# dengenver2_0.net
KiCad netlist of a schematic drawn in EAGLE
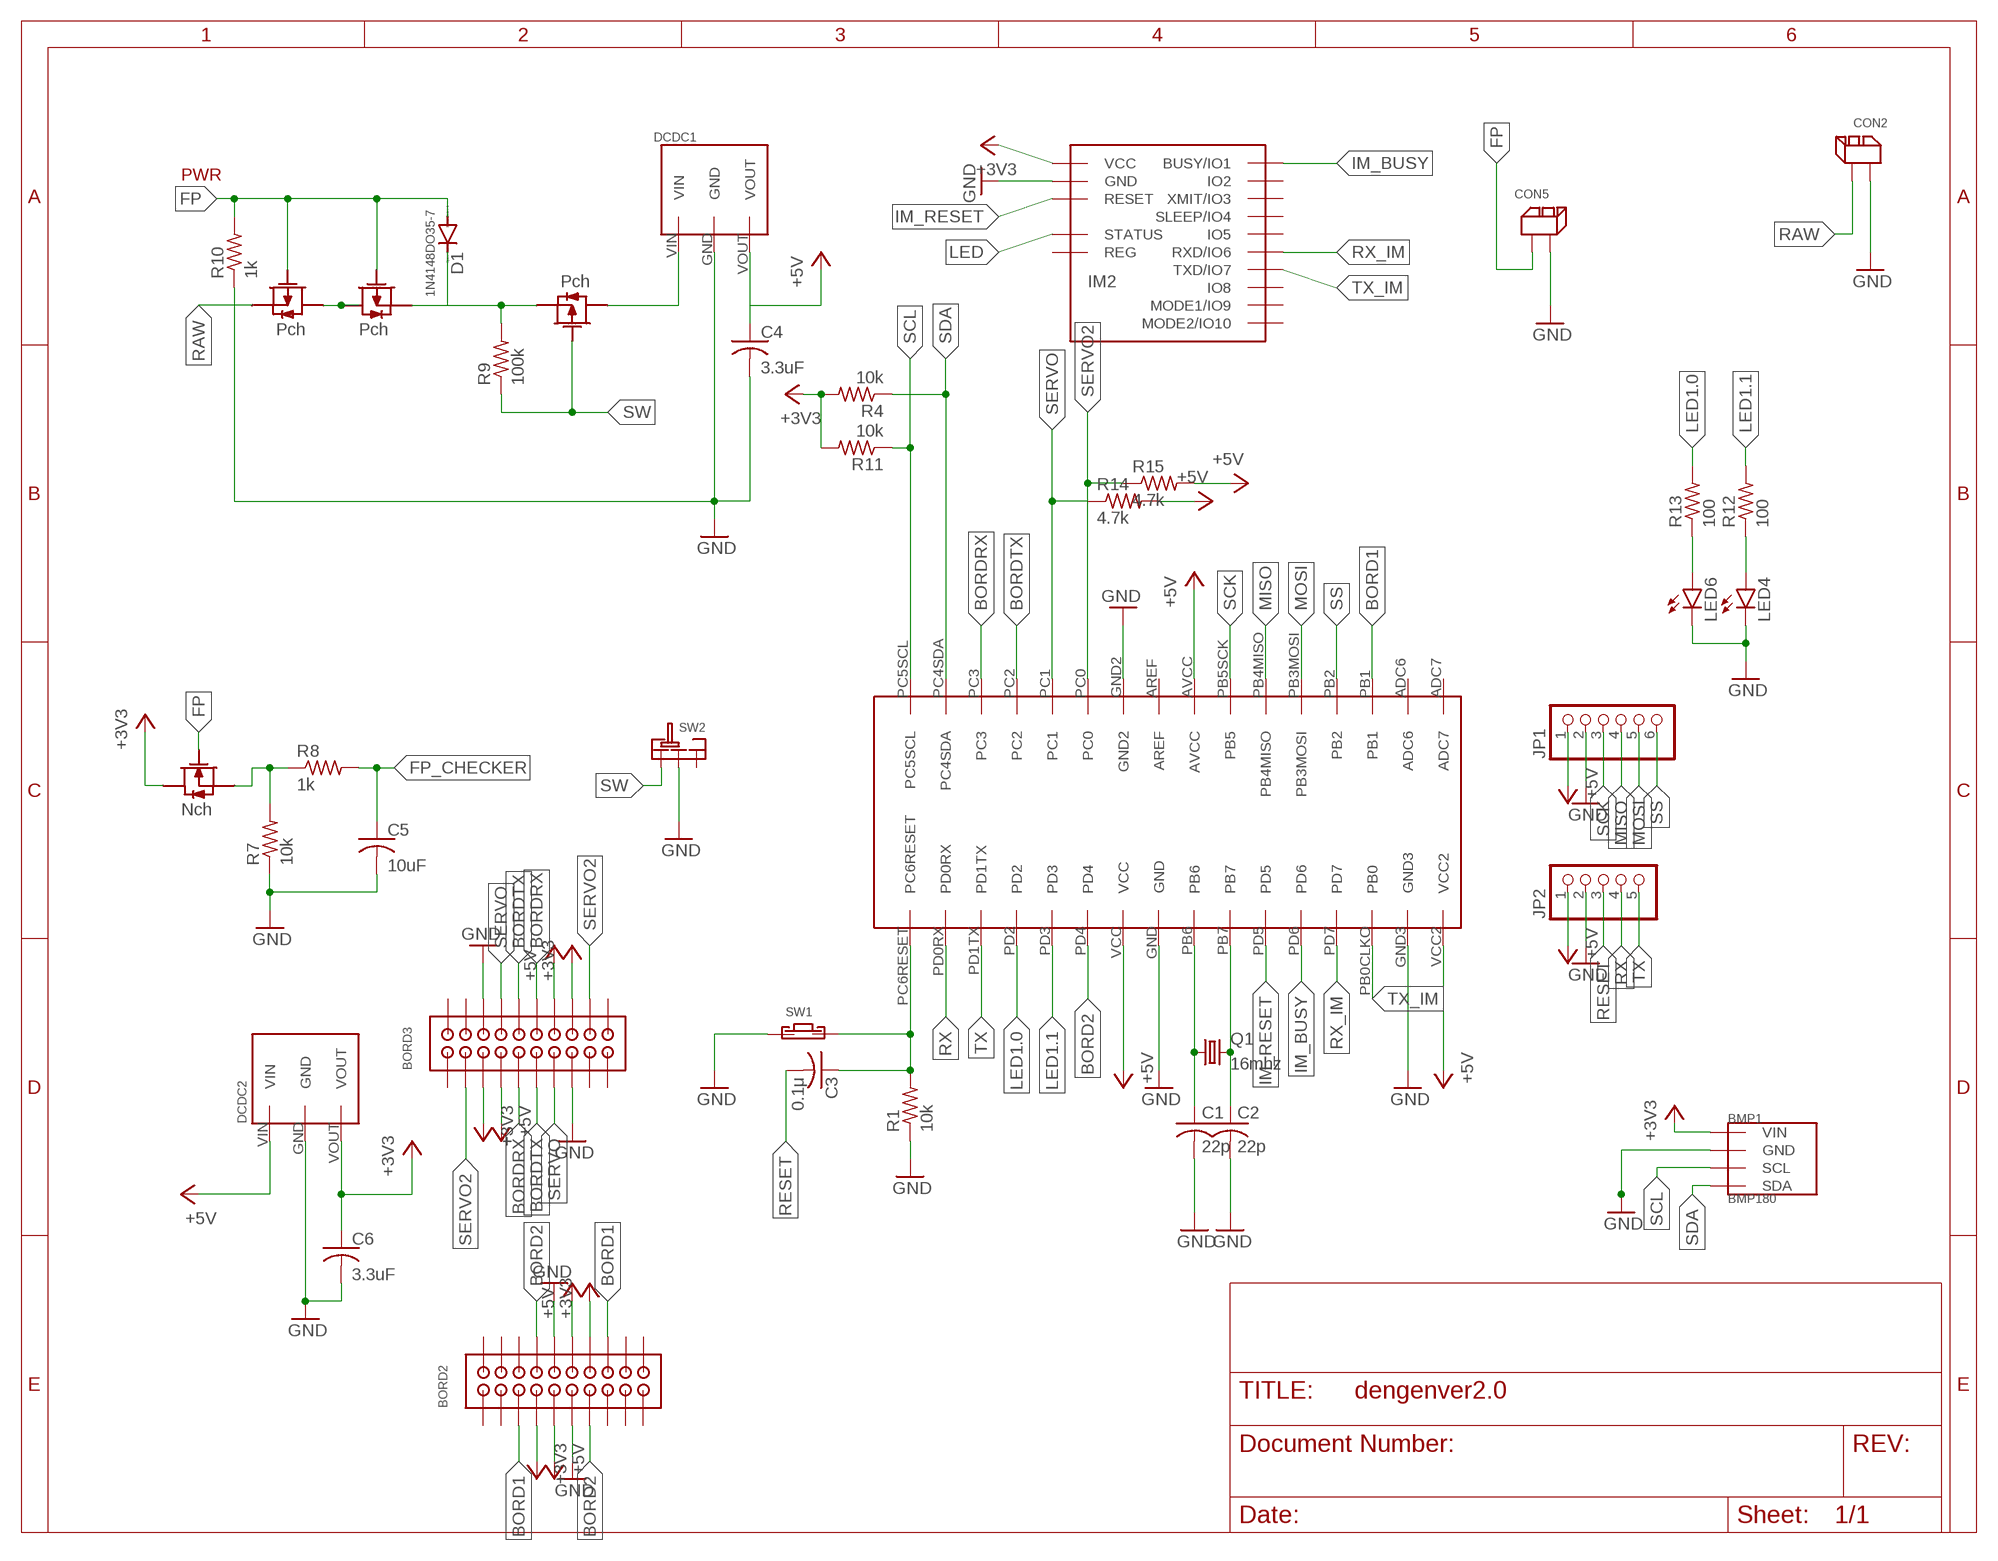
[diagram p0: schematic, sheet 1]

(export (version "E")
  (design (tool "Eeschema 10.0.6"))
  (components
    (comp (ref "BMP1")
      (value "BMP180")
      (footprint "eagle-import:GY-68")
      (libsource (lib "eagle-import") (part "BMP180"))
    )
    (comp (ref "BORD2")
      (value "2X10")
      (footprint "eagle-import:2X10")
      (libsource (lib "eagle-import") (part "2X10"))
    )
    (comp (ref "BORD3")
      (value "2X10")
      (footprint "eagle-import:2X10")
      (libsource (lib "eagle-import") (part "2X10"))
    )
    (comp (ref "C1")
      (value "22p")
      (footprint "eagle-import:C1608")
      (libsource (lib "eagle-import") (part "C-USC1608"))
    )
    (comp (ref "C2")
      (value "22p")
      (footprint "eagle-import:C1608")
      (libsource (lib "eagle-import") (part "C-USC1608"))
    )
    (comp (ref "C3")
      (value "0.1μ")
      (footprint "eagle-import:C1608")
      (libsource (lib "eagle-import") (part "C-USC1608"))
    )
    (comp (ref "C4")
      (value "3.3uF")
      (footprint "eagle-import:C1608")
      (libsource (lib "eagle-import") (part "C-USC1608"))
    )
    (comp (ref "C5")
      (value "10uF")
      (footprint "eagle-import:C1608")
      (libsource (lib "eagle-import") (part "C-USC1608"))
    )
    (comp (ref "C6")
      (value "3.3uF")
      (footprint "eagle-import:C1608")
      (libsource (lib "eagle-import") (part "C-USC1608"))
    )
    (comp (ref "CON2")
      (value "2PIN")
      (footprint "eagle-import:2PIN")
      (libsource (lib "eagle-import") (part "2PIN"))
    )
    (comp (ref "CON5")
      (value "2PIN")
      (footprint "eagle-import:2PIN")
      (libsource (lib "eagle-import") (part "2PIN"))
    )
    (comp (ref "D1")
      (value "1N4148DO35-7")
      (footprint "eagle-import:DO35-7")
      (libsource (lib "eagle-import") (part "1N4148DO35-7"))
    )
    (comp (ref "DCDC1")
      (value "5V1A_M78AR05-1")
      (footprint "eagle-import:5V1A_M78AR05-1")
      (libsource (lib "eagle-import") (part "5V1A_M78AR05-1"))
    )
    (comp (ref "DCDC2")
      (value "3.3V1A_M78AR033-1")
      (footprint "eagle-import:3.3V1A_M78AR033-1")
      (libsource (lib "eagle-import") (part "3.3V1A_M78AR033-1"))
    )
    (comp (ref "IM2")
      (value "IM920_IM920C")
      (footprint "eagle-import:IM920_IM920C")
      (libsource (lib "eagle-import") (part "IM920_IM920C"))
    )
    (comp (ref "JP1")
      (value "PINHD-1X6")
      (footprint "eagle-import:1X06")
      (libsource (lib "eagle-import") (part "PINHD-1X6"))
    )
    (comp (ref "JP2")
      (value "PINHD-1X5")
      (footprint "eagle-import:1X05")
      (libsource (lib "eagle-import") (part "PINHD-1X5"))
    )
    (comp (ref "LED4")
      (value "LED5MM")
      (footprint "eagle-import:LED5MM")
      (libsource (lib "eagle-import") (part "LED5MM"))
    )
    (comp (ref "LED6")
      (value "LED5MM")
      (footprint "eagle-import:LED5MM")
      (libsource (lib "eagle-import") (part "LED5MM"))
    )
    (comp (ref "Q1")
      (value "16mhz")
      (footprint "eagle-import:HC49UP")
      (libsource (lib "eagle-import") (part "CRYSTALHC49UP"))
    )
    (comp (ref "R1")
      (value "10k")
      (footprint "eagle-import:R0603")
      (libsource (lib "eagle-import") (part "R-US_R0603"))
    )
    (comp (ref "R4")
      (value "10k")
      (footprint "eagle-import:R0603")
      (libsource (lib "eagle-import") (part "R-US_R0603"))
    )
    (comp (ref "R7")
      (value "10k")
      (footprint "eagle-import:R0603")
      (libsource (lib "eagle-import") (part "R-US_R0603"))
    )
    (comp (ref "R8")
      (value "1k")
      (footprint "eagle-import:R0603")
      (libsource (lib "eagle-import") (part "R-US_R0603"))
    )
    (comp (ref "R9")
      (value "100k")
      (footprint "eagle-import:R0603")
      (libsource (lib "eagle-import") (part "R-US_R0603"))
    )
    (comp (ref "R10")
      (value "1k")
      (footprint "eagle-import:R0603")
      (libsource (lib "eagle-import") (part "R-US_R0603"))
    )
    (comp (ref "R11")
      (value "10k")
      (footprint "eagle-import:R0603")
      (libsource (lib "eagle-import") (part "R-US_R0603"))
    )
    (comp (ref "R12")
      (value "100")
      (footprint "eagle-import:R0603")
      (libsource (lib "eagle-import") (part "R-US_R0603"))
    )
    (comp (ref "R13")
      (value "100")
      (footprint "eagle-import:R0603")
      (libsource (lib "eagle-import") (part "R-US_R0603"))
    )
    (comp (ref "R14")
      (value "4.7k")
      (footprint "eagle-import:R0603")
      (libsource (lib "eagle-import") (part "R-US_R0603"))
    )
    (comp (ref "R15")
      (value "4.7k")
      (footprint "eagle-import:R0603")
      (libsource (lib "eagle-import") (part "R-US_R0603"))
    )
    (comp (ref "SW1")
      (value "TVAF06-A020B-R")
      (footprint "eagle-import:TVAF06-A020B-R")
      (libsource (lib "eagle-import") (part "TVAF06-A020B-R"))
    )
    (comp (ref "SW2")
      (value "SRIDE_SWITCH")
      (footprint "eagle-import:SRIDE_SWITCH")
      (libsource (lib "eagle-import") (part "SRIDE_SWITCH"))
    )
    (comp (ref "U$1")
      (value "ATMEGA328P-AU")
      (footprint "eagle-import:ATMEGA328P-AU")
      (libsource (lib "eagle-import") (part "ATMEGA328P-AU"))
    )
    (comp (ref "U$2")
      (value "2SJ681-PCH")
      (footprint "eagle-import:2SJ681")
      (libsource (lib "eagle-import") (part "2SJ681-PCH"))
    )
    (comp (ref "U$3")
      (value "2SK4017-NCH")
      (footprint "eagle-import:2SK4017")
      (libsource (lib "eagle-import") (part "2SK4017-NCH"))
    )
    (comp (ref "U$4")
      (value "2SJ681-PCH")
      (footprint "eagle-import:2SJ681")
      (libsource (lib "eagle-import") (part "2SJ681-PCH"))
    )
    (comp (ref "U$5")
      (value "2SJ681-PCH")
      (footprint "eagle-import:2SJ681")
      (libsource (lib "eagle-import") (part "2SJ681-PCH"))
    )
  )
  (nets
    (net (code "1") (name "+3V3") (class "Default")
      (node (ref "BMP1") (pin "P1") (pinfunction "VIN_P1") (pintype "bidirectional"))
      (node (ref "BORD2") (pin "P$14") (pinfunction "P$14_P$14") (pintype "bidirectional"))
      (node (ref "BORD2") (pin "P$7") (pinfunction "P$7_P$7") (pintype "bidirectional"))
      (node (ref "BORD3") (pin "P$16") (pinfunction "P$16_P$16") (pintype "bidirectional"))
      (node (ref "BORD3") (pin "P$5") (pinfunction "P$5_P$5") (pintype "bidirectional"))
      (node (ref "C6") (pin "1") (pinfunction "1_1") (pintype "passive"))
      (node (ref "DCDC2") (pin "VOUT") (pinfunction "VOUT_VOUT") (pintype "bidirectional"))
      (node (ref "IM2") (pin "$P17") (pinfunction "VCC_$P17") (pintype "bidirectional"))
      (node (ref "R11") (pin "2") (pinfunction "2_2") (pintype "passive"))
      (node (ref "R4") (pin "2") (pinfunction "2_2") (pintype "passive"))
      (node (ref "U$3") (pin "DRAIN") (pinfunction "DRAIN_DRAIN") (pintype "bidirectional"))
    )
    (net (code "2") (name "+5V") (class "Default")
      (node (ref "BORD2") (pin "P$12") (pinfunction "P$12_P$12") (pintype "bidirectional"))
      (node (ref "BORD2") (pin "P$9") (pinfunction "P$9_P$9") (pintype "bidirectional"))
      (node (ref "BORD3") (pin "P$14") (pinfunction "P$14_P$14") (pintype "bidirectional"))
      (node (ref "BORD3") (pin "P$7") (pinfunction "P$7_P$7") (pintype "bidirectional"))
      (node (ref "C4") (pin "1") (pinfunction "1_1") (pintype "passive"))
      (node (ref "DCDC1") (pin "VOUT") (pinfunction "VOUT_VOUT") (pintype "bidirectional"))
      (node (ref "DCDC2") (pin "VIN") (pinfunction "VIN_VIN") (pintype "bidirectional"))
      (node (ref "JP1") (pin "1") (pinfunction "1_1") (pintype "passive"))
      (node (ref "JP2") (pin "1") (pinfunction "1_1") (pintype "passive"))
      (node (ref "R14") (pin "2") (pinfunction "2_2") (pintype "passive"))
      (node (ref "R15") (pin "2") (pinfunction "2_2") (pintype "passive"))
      (node (ref "U$1") (pin "AVCC") (pinfunction "AVCC_AVCC") (pintype "bidirectional"))
      (node (ref "U$1") (pin "VCC") (pinfunction "VCC_VCC") (pintype "bidirectional"))
      (node (ref "U$1") (pin "VCC2") (pinfunction "VCC2_VCC2") (pintype "bidirectional"))
    )
    (net (code "3") (name "BORD1") (class "Default")
      (node (ref "BORD2") (pin "P$16") (pinfunction "P$16_P$16") (pintype "bidirectional"))
      (node (ref "BORD2") (pin "P$5") (pinfunction "P$5_P$5") (pintype "bidirectional"))
      (node (ref "U$1") (pin "PB1") (pinfunction "PB1_PB1") (pintype "bidirectional"))
    )
    (net (code "4") (name "BORD2") (class "Default")
      (node (ref "BORD2") (pin "P$13") (pinfunction "P$13_P$13") (pintype "bidirectional"))
      (node (ref "BORD2") (pin "P$8") (pinfunction "P$8_P$8") (pintype "bidirectional"))
      (node (ref "U$1") (pin "PD4") (pinfunction "PD4_PD4") (pintype "bidirectional"))
    )
    (net (code "5") (name "BORDRX") (class "Default")
      (node (ref "BORD3") (pin "P$12") (pinfunction "P$12_P$12") (pintype "bidirectional"))
      (node (ref "BORD3") (pin "P$9") (pinfunction "P$9_P$9") (pintype "bidirectional"))
      (node (ref "U$1") (pin "PC3") (pinfunction "PC3_PC3") (pintype "bidirectional"))
    )
    (net (code "6") (name "BORDTX") (class "Default")
      (node (ref "BORD3") (pin "P$10") (pinfunction "P$10_P$10") (pintype "bidirectional"))
      (node (ref "BORD3") (pin "P$11") (pinfunction "P$11_P$11") (pintype "bidirectional"))
      (node (ref "U$1") (pin "PC2") (pinfunction "PC2_PC2") (pintype "bidirectional"))
    )
    (net (code "7") (name "FP") (class "Default")
      (node (ref "CON5") (pin "P$1") (pinfunction "P$1_P$1") (pintype "bidirectional"))
      (node (ref "D1") (pin "A") (pinfunction "A_A") (pintype "passive"))
      (node (ref "R10") (pin "2") (pinfunction "2_2") (pintype "passive"))
      (node (ref "U$2") (pin "GATE") (pinfunction "GATE_GATE") (pintype "bidirectional"))
      (node (ref "U$3") (pin "GATE") (pinfunction "GATE_GATE") (pintype "bidirectional"))
      (node (ref "U$4") (pin "GATE") (pinfunction "GATE_GATE") (pintype "bidirectional"))
    )
    (net (code "8") (name "FP_CHECKER") (class "Default")
      (node (ref "C5") (pin "1") (pinfunction "1_1") (pintype "passive"))
      (node (ref "R8") (pin "2") (pinfunction "2_2") (pintype "passive"))
    )
    (net (code "9") (name "GND") (class "Default")
      (node (ref "BMP1") (pin "P2") (pinfunction "GND_P2") (pintype "bidirectional"))
      (node (ref "BORD2") (pin "P$10") (pinfunction "P$10_P$10") (pintype "bidirectional"))
      (node (ref "BORD2") (pin "P$11") (pinfunction "P$11_P$11") (pintype "bidirectional"))
      (node (ref "BORD3") (pin "P$15") (pinfunction "P$15_P$15") (pintype "bidirectional"))
      (node (ref "BORD3") (pin "P$6") (pinfunction "P$6_P$6") (pintype "bidirectional"))
      (node (ref "C1") (pin "2") (pinfunction "2_2") (pintype "passive"))
      (node (ref "C2") (pin "2") (pinfunction "2_2") (pintype "passive"))
      (node (ref "C4") (pin "2") (pinfunction "2_2") (pintype "passive"))
      (node (ref "C5") (pin "2") (pinfunction "2_2") (pintype "passive"))
      (node (ref "C6") (pin "2") (pinfunction "2_2") (pintype "passive"))
      (node (ref "CON2") (pin "P$1") (pinfunction "P$1_P$1") (pintype "bidirectional"))
      (node (ref "CON5") (pin "P$2") (pinfunction "P$2_P$2") (pintype "bidirectional"))
      (node (ref "DCDC1") (pin "GND") (pinfunction "GND_GND") (pintype "bidirectional"))
      (node (ref "DCDC2") (pin "GND") (pinfunction "GND_GND") (pintype "bidirectional"))
      (node (ref "IM2") (pin "$P18") (pinfunction "GND_$P18") (pintype "bidirectional"))
      (node (ref "JP1") (pin "2") (pinfunction "2_2") (pintype "passive"))
      (node (ref "JP2") (pin "2") (pinfunction "2_2") (pintype "passive"))
      (node (ref "LED4") (pin "K") (pinfunction "C_K") (pintype "passive"))
      (node (ref "LED6") (pin "K") (pinfunction "C_K") (pintype "passive"))
      (node (ref "R1") (pin "1") (pinfunction "1_1") (pintype "passive"))
      (node (ref "R10") (pin "1") (pinfunction "1_1") (pintype "passive"))
      (node (ref "R7") (pin "1") (pinfunction "1_1") (pintype "passive"))
      (node (ref "SW1") (pin "P$1") (pinfunction "P$1_P$1") (pintype "bidirectional"))
      (node (ref "SW2") (pin "LR") (pinfunction "LR_LR") (pintype "bidirectional"))
      (node (ref "U$1") (pin "GND") (pinfunction "GND_GND") (pintype "bidirectional"))
      (node (ref "U$1") (pin "GND2") (pinfunction "GND2_GND2") (pintype "bidirectional"))
      (node (ref "U$1") (pin "GND3") (pinfunction "GND3_GND3") (pintype "bidirectional"))
    )
    (net (code "10") (name "IM_BUSY") (class "Default")
      (node (ref "IM2") (pin "$P1") (pinfunction "BUSY/IO1_$P1") (pintype "bidirectional"))
      (node (ref "U$1") (pin "PD6") (pinfunction "PD6_PD6") (pintype "bidirectional"))
    )
    (net (code "11") (name "IM_RESET") (class "Default")
      (node (ref "IM2") (pin "$P19") (pinfunction "RESET_$P19") (pintype "bidirectional"))
      (node (ref "U$1") (pin "PD5") (pinfunction "PD5_PD5") (pintype "bidirectional"))
    )
    (net (code "12") (name "LED") (class "Default")
      (node (ref "IM2") (pin "$P15") (pinfunction "STATUS_$P15") (pintype "bidirectional"))
    )
    (net (code "13") (name "LED1.0") (class "Default")
      (node (ref "R13") (pin "2") (pinfunction "2_2") (pintype "passive"))
      (node (ref "U$1") (pin "PD2") (pinfunction "PD2_PD2") (pintype "bidirectional"))
    )
    (net (code "14") (name "LED1.1") (class "Default")
      (node (ref "R12") (pin "2") (pinfunction "2_2") (pintype "passive"))
      (node (ref "U$1") (pin "PD3") (pinfunction "PD3_PD3") (pintype "bidirectional"))
    )
    (net (code "15") (name "MISO") (class "Default")
      (node (ref "JP1") (pin "4") (pinfunction "4_4") (pintype "passive"))
      (node (ref "U$1") (pin "PB4MISO") (pinfunction "PB4MISO_PB4MISO") (pintype "bidirectional"))
    )
    (net (code "16") (name "MOSI") (class "Default")
      (node (ref "JP1") (pin "5") (pinfunction "5_5") (pintype "passive"))
      (node (ref "U$1") (pin "PB3MOSI") (pinfunction "PB3MOSI_PB3MOSI") (pintype "bidirectional"))
    )
    (net (code "17") (name "Net-(C1-Pad1)") (class "Default")
      (node (ref "C1") (pin "1") (pinfunction "1_1") (pintype "passive"))
      (node (ref "Q1") (pin "1") (pinfunction "1_1") (pintype "passive"))
      (node (ref "U$1") (pin "PB6") (pinfunction "PB6_PB6") (pintype "bidirectional"))
    )
    (net (code "18") (name "Net-(C2-Pad1)") (class "Default")
      (node (ref "C2") (pin "1") (pinfunction "1_1") (pintype "passive"))
      (node (ref "Q1") (pin "2") (pinfunction "2_2") (pintype "passive"))
      (node (ref "U$1") (pin "PB7") (pinfunction "PB7_PB7") (pintype "bidirectional"))
    )
    (net (code "19") (name "Net-(C3-Pad1)") (class "Default")
      (node (ref "C3") (pin "1") (pinfunction "1_1") (pintype "passive"))
      (node (ref "R1") (pin "2") (pinfunction "2_2") (pintype "passive"))
      (node (ref "SW1") (pin "P$2") (pinfunction "P$2_P$2") (pintype "bidirectional"))
      (node (ref "U$1") (pin "PC6RESET") (pinfunction "PC6RESET_PC6RESET") (pintype "bidirectional"))
    )
    (net (code "20") (name "Net-(D1-PadC)") (class "Default")
      (node (ref "D1") (pin "C") (pinfunction "C_C") (pintype "passive"))
      (node (ref "R9") (pin "2") (pinfunction "2_2") (pintype "passive"))
      (node (ref "U$4") (pin "SOURCE") (pinfunction "SOURCE_SOURCE") (pintype "bidirectional"))
      (node (ref "U$5") (pin "SOURCE") (pinfunction "SOURCE_SOURCE") (pintype "bidirectional"))
    )
    (net (code "21") (name "Net-(DCDC1-PadVIN)") (class "Default")
      (node (ref "DCDC1") (pin "VIN") (pinfunction "VIN_VIN") (pintype "bidirectional"))
      (node (ref "U$5") (pin "DRAIN") (pinfunction "DRAIN_DRAIN") (pintype "bidirectional"))
    )
    (net (code "22") (name "Net-(LED4-PadA)") (class "Default")
      (node (ref "LED4") (pin "A") (pinfunction "A_A") (pintype "passive"))
      (node (ref "R12") (pin "1") (pinfunction "1_1") (pintype "passive"))
    )
    (net (code "23") (name "Net-(LED6-PadA)") (class "Default")
      (node (ref "LED6") (pin "A") (pinfunction "A_A") (pintype "passive"))
      (node (ref "R13") (pin "1") (pinfunction "1_1") (pintype "passive"))
    )
    (net (code "24") (name "Net-(R7-Pad2)") (class "Default")
      (node (ref "R7") (pin "2") (pinfunction "2_2") (pintype "passive"))
      (node (ref "R8") (pin "1") (pinfunction "1_1") (pintype "passive"))
      (node (ref "U$3") (pin "SOURCE") (pinfunction "SOURCE_SOURCE") (pintype "bidirectional"))
    )
    (net (code "25") (name "Net-(U$2-PadDRAIN)") (class "Default")
      (node (ref "U$2") (pin "DRAIN") (pinfunction "DRAIN_DRAIN") (pintype "bidirectional"))
      (node (ref "U$4") (pin "DRAIN") (pinfunction "DRAIN_DRAIN") (pintype "bidirectional"))
    )
    (net (code "26") (name "RAW") (class "Default")
      (node (ref "CON2") (pin "P$2") (pinfunction "P$2_P$2") (pintype "bidirectional"))
      (node (ref "U$2") (pin "SOURCE") (pinfunction "SOURCE_SOURCE") (pintype "bidirectional"))
    )
    (net (code "27") (name "RESET") (class "Default")
      (node (ref "C3") (pin "2") (pinfunction "2_2") (pintype "passive"))
      (node (ref "JP2") (pin "3") (pinfunction "3_3") (pintype "passive"))
    )
    (net (code "28") (name "RX") (class "Default")
      (node (ref "JP2") (pin "4") (pinfunction "4_4") (pintype "passive"))
      (node (ref "U$1") (pin "PD0RX") (pinfunction "PD0RX_PD0RX") (pintype "bidirectional"))
    )
    (net (code "29") (name "RX_IM") (class "Default")
      (node (ref "IM2") (pin "$P6") (pinfunction "RXD/IO6_$P6") (pintype "bidirectional"))
      (node (ref "U$1") (pin "PD7") (pinfunction "PD7_PD7") (pintype "bidirectional"))
    )
    (net (code "30") (name "SCK") (class "Default")
      (node (ref "JP1") (pin "3") (pinfunction "3_3") (pintype "passive"))
      (node (ref "U$1") (pin "PB5SCK") (pinfunction "PB5_PB5SCK") (pintype "bidirectional"))
    )
    (net (code "31") (name "SCL") (class "Default")
      (node (ref "BMP1") (pin "P3") (pinfunction "SCL_P3") (pintype "bidirectional"))
      (node (ref "R11") (pin "1") (pinfunction "1_1") (pintype "passive"))
      (node (ref "U$1") (pin "PC5SCL") (pinfunction "PC5SCL_PC5SCL") (pintype "bidirectional"))
    )
    (net (code "32") (name "SDA") (class "Default")
      (node (ref "BMP1") (pin "P4") (pinfunction "SDA_P4") (pintype "bidirectional"))
      (node (ref "R4") (pin "1") (pinfunction "1_1") (pintype "passive"))
      (node (ref "U$1") (pin "PC4SDA") (pinfunction "PC4SDA_PC4SDA") (pintype "bidirectional"))
    )
    (net (code "33") (name "SERVO") (class "Default")
      (node (ref "BORD3") (pin "P$13") (pinfunction "P$13_P$13") (pintype "bidirectional"))
      (node (ref "BORD3") (pin "P$8") (pinfunction "P$8_P$8") (pintype "bidirectional"))
      (node (ref "R14") (pin "1") (pinfunction "1_1") (pintype "passive"))
      (node (ref "U$1") (pin "PC1") (pinfunction "PC1_PC1") (pintype "bidirectional"))
    )
    (net (code "34") (name "SERVO2") (class "Default")
      (node (ref "BORD3") (pin "P$18") (pinfunction "P$18_P$18") (pintype "bidirectional"))
      (node (ref "BORD3") (pin "P$3") (pinfunction "P$3_P$3") (pintype "bidirectional"))
      (node (ref "R15") (pin "1") (pinfunction "1_1") (pintype "passive"))
      (node (ref "U$1") (pin "PC0") (pinfunction "PC0_PC0") (pintype "bidirectional"))
    )
    (net (code "35") (name "SS") (class "Default")
      (node (ref "JP1") (pin "6") (pinfunction "6_6") (pintype "passive"))
      (node (ref "U$1") (pin "PB2") (pinfunction "PB2_PB2") (pintype "bidirectional"))
    )
    (net (code "36") (name "SW") (class "Default")
      (node (ref "R9") (pin "1") (pinfunction "1_1") (pintype "passive"))
      (node (ref "SW2") (pin "L") (pinfunction "L_L") (pintype "bidirectional"))
      (node (ref "U$5") (pin "GATE") (pinfunction "GATE_GATE") (pintype "bidirectional"))
    )
    (net (code "37") (name "TX") (class "Default")
      (node (ref "JP2") (pin "5") (pinfunction "5_5") (pintype "passive"))
      (node (ref "U$1") (pin "PD1TX") (pinfunction "PD1TX_PD1TX") (pintype "bidirectional"))
    )
    (net (code "38") (name "TX_IM") (class "Default")
      (node (ref "IM2") (pin "$P7") (pinfunction "TXD/IO7_$P7") (pintype "bidirectional"))
      (node (ref "U$1") (pin "PB0CLKO") (pinfunction "PB0_PB0CLKO") (pintype "bidirectional"))
    )
    (net (code "39") (name "unconnected-(BORD2-PadP$1)") (class "Default")
      (node (ref "BORD2") (pin "P$1") (pinfunction "P$1_P$1") (pintype "bidirectional"))
    )
    (net (code "40") (name "unconnected-(BORD2-PadP$2)") (class "Default")
      (node (ref "BORD2") (pin "P$2") (pinfunction "P$2_P$2") (pintype "bidirectional"))
    )
    (net (code "41") (name "unconnected-(BORD2-PadP$3)") (class "Default")
      (node (ref "BORD2") (pin "P$3") (pinfunction "P$3_P$3") (pintype "bidirectional"))
    )
    (net (code "42") (name "unconnected-(BORD2-PadP$4)") (class "Default")
      (node (ref "BORD2") (pin "P$4") (pinfunction "P$4_P$4") (pintype "bidirectional"))
    )
    (net (code "43") (name "unconnected-(BORD2-PadP$6)") (class "Default")
      (node (ref "BORD2") (pin "P$6") (pinfunction "P$6_P$6") (pintype "bidirectional"))
    )
    (net (code "44") (name "unconnected-(BORD2-PadP$15)") (class "Default")
      (node (ref "BORD2") (pin "P$15") (pinfunction "P$15_P$15") (pintype "bidirectional"))
    )
    (net (code "45") (name "unconnected-(BORD2-PadP$17)") (class "Default")
      (node (ref "BORD2") (pin "P$17") (pinfunction "P$17_P$17") (pintype "bidirectional"))
    )
    (net (code "46") (name "unconnected-(BORD2-PadP$18)") (class "Default")
      (node (ref "BORD2") (pin "P$18") (pinfunction "P$18_P$18") (pintype "bidirectional"))
    )
    (net (code "47") (name "unconnected-(BORD2-PadP$19)") (class "Default")
      (node (ref "BORD2") (pin "P$19") (pinfunction "P$19_P$19") (pintype "bidirectional"))
    )
    (net (code "48") (name "unconnected-(BORD2-PadP$20)") (class "Default")
      (node (ref "BORD2") (pin "P$20") (pinfunction "P$20_P$20") (pintype "bidirectional"))
    )
    (net (code "49") (name "unconnected-(BORD3-PadP$1)") (class "Default")
      (node (ref "BORD3") (pin "P$1") (pinfunction "P$1_P$1") (pintype "bidirectional"))
    )
    (net (code "50") (name "unconnected-(BORD3-PadP$2)") (class "Default")
      (node (ref "BORD3") (pin "P$2") (pinfunction "P$2_P$2") (pintype "bidirectional"))
    )
    (net (code "51") (name "unconnected-(BORD3-PadP$4)") (class "Default")
      (node (ref "BORD3") (pin "P$4") (pinfunction "P$4_P$4") (pintype "bidirectional"))
    )
    (net (code "52") (name "unconnected-(BORD3-PadP$17)") (class "Default")
      (node (ref "BORD3") (pin "P$17") (pinfunction "P$17_P$17") (pintype "bidirectional"))
    )
    (net (code "53") (name "unconnected-(BORD3-PadP$19)") (class "Default")
      (node (ref "BORD3") (pin "P$19") (pinfunction "P$19_P$19") (pintype "bidirectional"))
    )
    (net (code "54") (name "unconnected-(BORD3-PadP$20)") (class "Default")
      (node (ref "BORD3") (pin "P$20") (pinfunction "P$20_P$20") (pintype "bidirectional"))
    )
    (net (code "55") (name "unconnected-(IM2-IO2-Pad$P2)") (class "Default")
      (node (ref "IM2") (pin "$P2") (pinfunction "IO2_$P2") (pintype "bidirectional"))
    )
    (net (code "56") (name "unconnected-(IM2-IO5-Pad$P5)") (class "Default")
      (node (ref "IM2") (pin "$P5") (pinfunction "IO5_$P5") (pintype "bidirectional"))
    )
    (net (code "57") (name "unconnected-(IM2-IO8-Pad$P8)") (class "Default")
      (node (ref "IM2") (pin "$P8") (pinfunction "IO8_$P8") (pintype "bidirectional"))
    )
    (net (code "58") (name "unconnected-(IM2-MODE1{slash}IO9-Pad$P9)") (class "Default")
      (node (ref "IM2") (pin "$P9") (pinfunction "MODE1/IO9_$P9") (pintype "bidirectional"))
    )
    (net (code "59") (name "unconnected-(IM2-MODE2{slash}IO10-Pad$P10)") (class "Default")
      (node (ref "IM2") (pin "$P10") (pinfunction "MODE2/IO10_$P10") (pintype "bidirectional"))
    )
    (net (code "60") (name "unconnected-(IM2-REG-Pad$P16)") (class "Default")
      (node (ref "IM2") (pin "$P16") (pinfunction "REG_$P16") (pintype "bidirectional"))
    )
    (net (code "61") (name "unconnected-(IM2-SLEEP{slash}IO4-Pad$P4)") (class "Default")
      (node (ref "IM2") (pin "$P4") (pinfunction "SLEEP/IO4_$P4") (pintype "bidirectional"))
    )
    (net (code "62") (name "unconnected-(IM2-XMIT{slash}IO3-Pad$P3)") (class "Default")
      (node (ref "IM2") (pin "$P3") (pinfunction "XMIT/IO3_$P3") (pintype "bidirectional"))
    )
    (net (code "63") (name "unconnected-(SW2-PadR)") (class "Default")
      (node (ref "SW2") (pin "R") (pinfunction "R_R") (pintype "bidirectional"))
    )
    (net (code "64") (name "unconnected-(U$1-PadADC6)") (class "Default")
      (node (ref "U$1") (pin "ADC6") (pinfunction "ADC6_ADC6") (pintype "bidirectional"))
    )
    (net (code "65") (name "unconnected-(U$1-PadADC7)") (class "Default")
      (node (ref "U$1") (pin "ADC7") (pinfunction "ADC7_ADC7") (pintype "bidirectional"))
    )
    (net (code "66") (name "unconnected-(U$1-PadAREF)") (class "Default")
      (node (ref "U$1") (pin "AREF") (pinfunction "AREF_AREF") (pintype "bidirectional"))
    )
  )
)
